# Bitsy_Display_Add-On.net
KiCad netlist of a schematic drawn in EAGLE
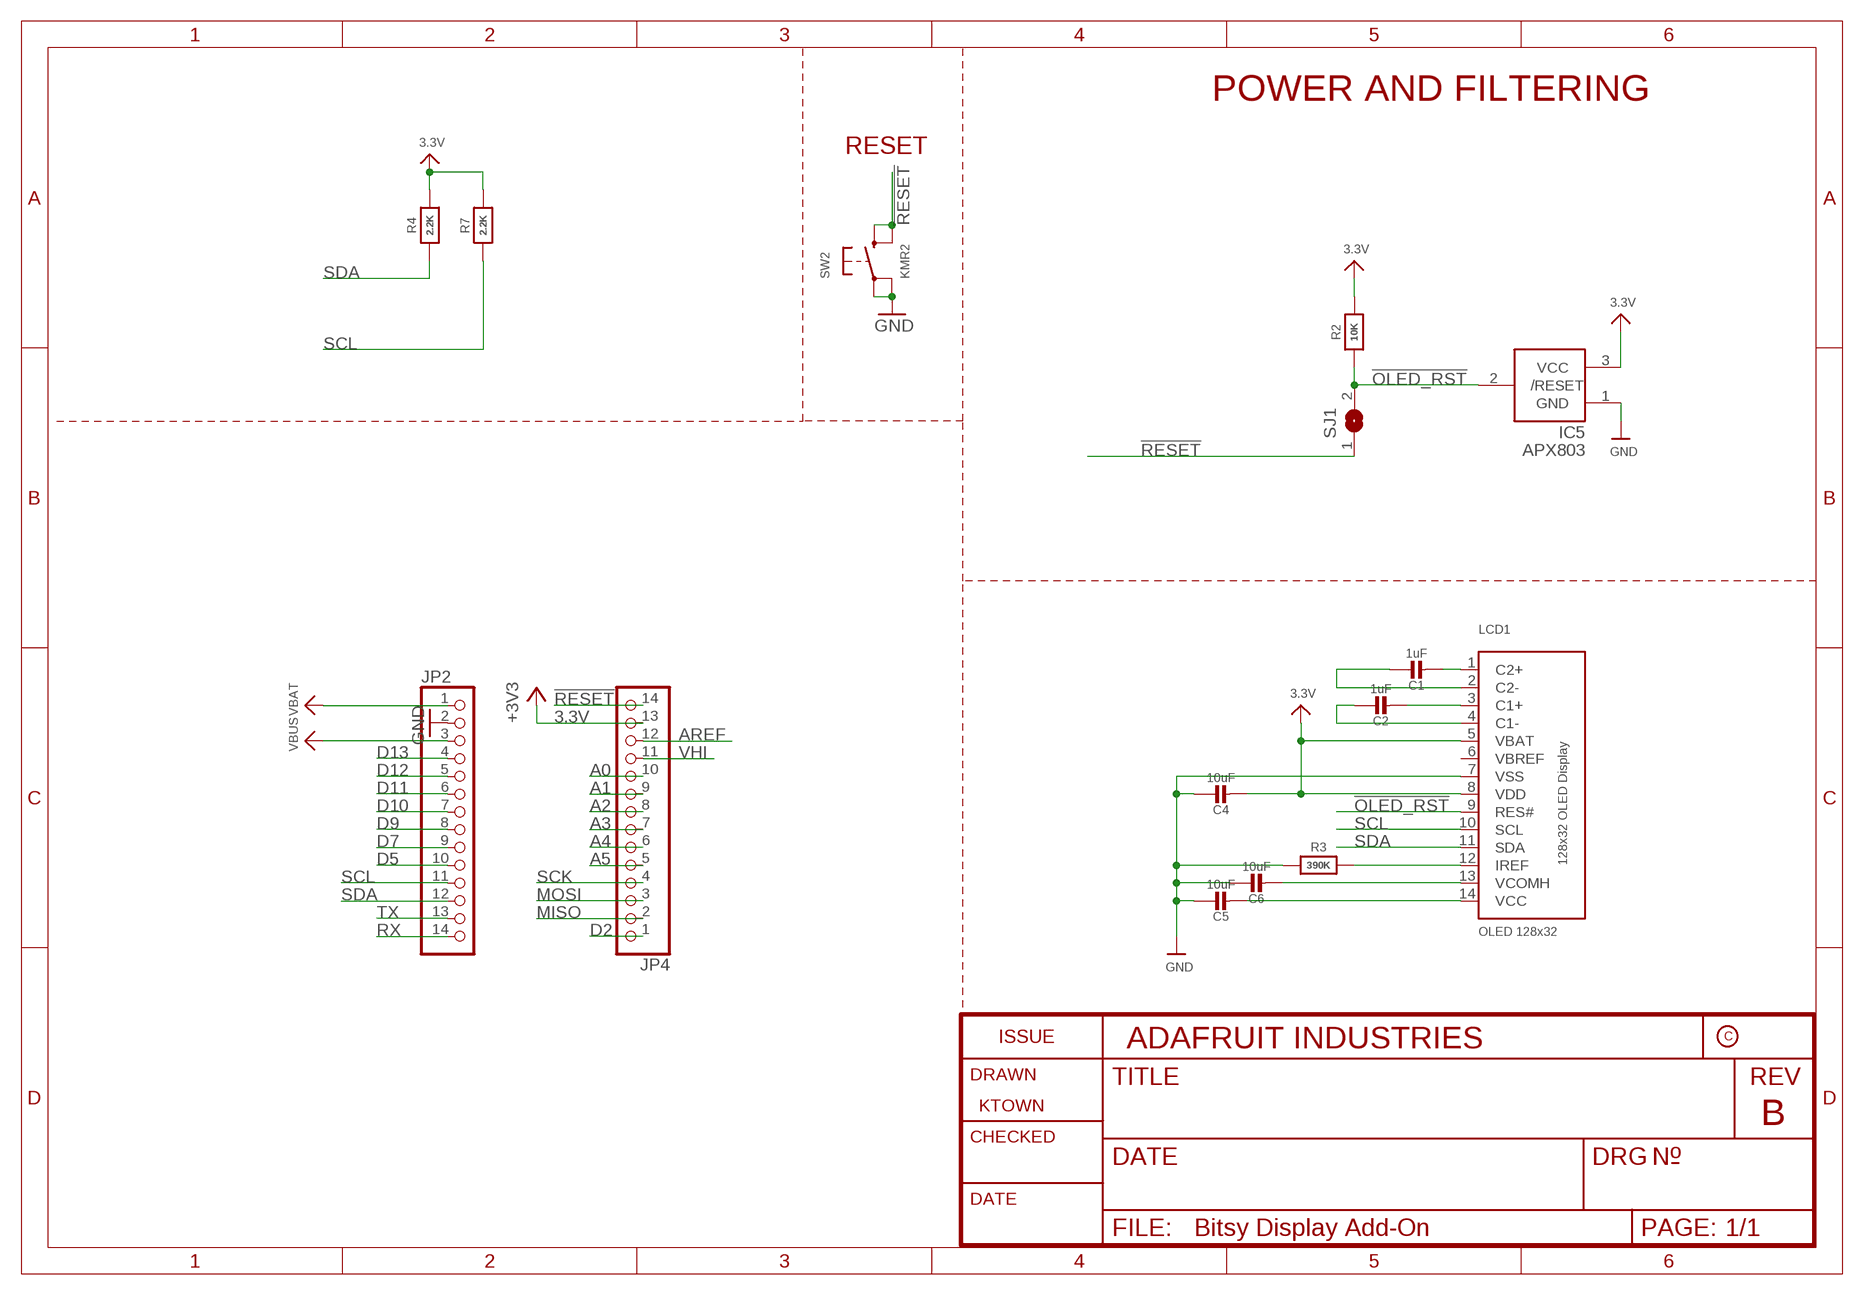
[diagram p0: schematic, sheet 1]

(export (version "E")
  (design (tool "Eeschema 10.0.6"))
  (components
    (comp (ref "C1")
      (value "1uF")
      (footprint "eagle-import:0805-NO")
      (libsource (lib "eagle-import") (part "CAP_CERAMIC0805-NOOUTLINE"))
    )
    (comp (ref "C2")
      (value "1uF")
      (footprint "eagle-import:0805-NO")
      (libsource (lib "eagle-import") (part "CAP_CERAMIC0805-NOOUTLINE"))
    )
    (comp (ref "C4")
      (value "10uF")
      (footprint "eagle-import:0805-NO")
      (libsource (lib "eagle-import") (part "CAP_CERAMIC0805-NOOUTLINE"))
    )
    (comp (ref "C5")
      (value "10uF")
      (footprint "eagle-import:0805-NO")
      (libsource (lib "eagle-import") (part "CAP_CERAMIC0805-NOOUTLINE"))
    )
    (comp (ref "C6")
      (value "10uF")
      (footprint "eagle-import:0805-NO")
      (libsource (lib "eagle-import") (part "CAP_CERAMIC0805-NOOUTLINE"))
    )
    (comp (ref "IC5")
      (value "APX803")
      (footprint "eagle-import:SOT23")
      (libsource (lib "eagle-import") (part "AXP083-SAG"))
    )
    (comp (ref "JP2")
      (value "HEADER-1X14")
      (footprint "eagle-import:1X14_ROUND70")
      (libsource (lib "eagle-import") (part "HEADER-1X14"))
    )
    (comp (ref "JP4")
      (value "HEADER-1X14")
      (footprint "eagle-import:1X14_ROUND70")
      (libsource (lib "eagle-import") (part "HEADER-1X14"))
    )
    (comp (ref "LCD1")
      (value "OLED 128x32")
      (footprint "eagle-import:UG-2832HSWEG02_WRAPUNDER")
      (libsource (lib "eagle-import") (part "DISP_OLED_UG-2832HSWEG02"))
    )
    (comp (ref "R2")
      (value "10K")
      (footprint "eagle-import:_0805MP")
      (libsource (lib "eagle-import") (part "RESISTOR_0805MP"))
    )
    (comp (ref "R3")
      (value "390K")
      (footprint "eagle-import:0805-NO")
      (libsource (lib "eagle-import") (part "RESISTOR0805_NOOUTLINE"))
    )
    (comp (ref "R4")
      (value "2.2K")
      (footprint "eagle-import:0805-NO")
      (libsource (lib "eagle-import") (part "RESISTOR0805_NOOUTLINE"))
    )
    (comp (ref "R7")
      (value "2.2K")
      (footprint "eagle-import:0805-NO")
      (libsource (lib "eagle-import") (part "RESISTOR0805_NOOUTLINE"))
    )
    (comp (ref "SJ1")
      (value "SOLDERJUMPER")
      (footprint "eagle-import:SOLDERJUMPER_ARROW_NOPASTE")
      (libsource (lib "eagle-import") (part "SOLDERJUMPER"))
    )
    (comp (ref "SW2")
      (value "KMR2")
      (footprint "eagle-import:BTN_KMR2_4.6X2.8")
      (libsource (lib "eagle-import") (part "SWITCH_TACT_SMT4.6X2.8"))
    )
  )
  (nets
    (net (code "1") (name "+3V3") (class "Default")
      (node (ref "C4") (pin "2") (pinfunction "2_2") (pintype "passive"))
      (node (ref "IC5") (pin "3") (pinfunction "VCC_3") (pintype "power_in"))
      (node (ref "JP4") (pin "13") (pinfunction "13_13") (pintype "passive"))
      (node (ref "LCD1") (pin "5") (pinfunction "VBAT_5") (pintype "power_in"))
      (node (ref "LCD1") (pin "8") (pinfunction "VDD_8") (pintype "power_in"))
      (node (ref "R2") (pin "2") (pinfunction "2_2") (pintype "passive"))
      (node (ref "R4") (pin "2") (pinfunction "2_2") (pintype "passive"))
      (node (ref "R7") (pin "2") (pinfunction "2_2") (pintype "passive"))
    )
    (net (code "2") (name "/A0") (class "Default")
      (node (ref "JP4") (pin "10") (pinfunction "10_10") (pintype "passive"))
    )
    (net (code "3") (name "/A1") (class "Default")
      (node (ref "JP4") (pin "9") (pinfunction "9_9") (pintype "passive"))
    )
    (net (code "4") (name "/A2") (class "Default")
      (node (ref "JP4") (pin "8") (pinfunction "8_8") (pintype "passive"))
    )
    (net (code "5") (name "/A3") (class "Default")
      (node (ref "JP4") (pin "7") (pinfunction "7_7") (pintype "passive"))
    )
    (net (code "6") (name "/A4") (class "Default")
      (node (ref "JP4") (pin "6") (pinfunction "6_6") (pintype "passive"))
    )
    (net (code "7") (name "/A5") (class "Default")
      (node (ref "JP4") (pin "5") (pinfunction "5_5") (pintype "passive"))
    )
    (net (code "8") (name "/AREF") (class "Default")
      (node (ref "JP4") (pin "12") (pinfunction "12_12") (pintype "passive"))
    )
    (net (code "9") (name "/D2") (class "Default")
      (node (ref "JP4") (pin "1") (pinfunction "1_1") (pintype "passive"))
    )
    (net (code "10") (name "/D5") (class "Default")
      (node (ref "JP2") (pin "10") (pinfunction "10_10") (pintype "passive"))
    )
    (net (code "11") (name "/D7") (class "Default")
      (node (ref "JP2") (pin "9") (pinfunction "9_9") (pintype "passive"))
    )
    (net (code "12") (name "/D9") (class "Default")
      (node (ref "JP2") (pin "8") (pinfunction "8_8") (pintype "passive"))
    )
    (net (code "13") (name "/D10") (class "Default")
      (node (ref "JP2") (pin "7") (pinfunction "7_7") (pintype "passive"))
    )
    (net (code "14") (name "/D11") (class "Default")
      (node (ref "JP2") (pin "6") (pinfunction "6_6") (pintype "passive"))
    )
    (net (code "15") (name "/D12") (class "Default")
      (node (ref "JP2") (pin "5") (pinfunction "5_5") (pintype "passive"))
    )
    (net (code "16") (name "/D13") (class "Default")
      (node (ref "JP2") (pin "4") (pinfunction "4_4") (pintype "passive"))
    )
    (net (code "17") (name "/MISO") (class "Default")
      (node (ref "JP4") (pin "2") (pinfunction "2_2") (pintype "passive"))
    )
    (net (code "18") (name "/MOSI") (class "Default")
      (node (ref "JP4") (pin "3") (pinfunction "3_3") (pintype "passive"))
    )
    (net (code "19") (name "/RX") (class "Default")
      (node (ref "JP2") (pin "14") (pinfunction "14_14") (pintype "passive"))
    )
    (net (code "20") (name "/SCK") (class "Default")
      (node (ref "JP4") (pin "4") (pinfunction "4_4") (pintype "passive"))
    )
    (net (code "21") (name "/SCL") (class "Default")
      (node (ref "JP2") (pin "11") (pinfunction "11_11") (pintype "passive"))
      (node (ref "LCD1") (pin "10") (pinfunction "SCL_10") (pintype "bidirectional"))
      (node (ref "R7") (pin "1") (pinfunction "1_1") (pintype "passive"))
    )
    (net (code "22") (name "/SDA") (class "Default")
      (node (ref "JP2") (pin "12") (pinfunction "12_12") (pintype "passive"))
      (node (ref "LCD1") (pin "11") (pinfunction "SDA_11") (pintype "bidirectional"))
      (node (ref "R4") (pin "1") (pinfunction "1_1") (pintype "passive"))
    )
    (net (code "23") (name "/TX") (class "Default")
      (node (ref "JP2") (pin "13") (pinfunction "13_13") (pintype "passive"))
    )
    (net (code "24") (name "/VBREF") (class "Default")
      (node (ref "LCD1") (pin "6") (pinfunction "VBREF_6") (pintype "power_in"))
    )
    (net (code "25") (name "/VHI") (class "Default")
      (node (ref "JP4") (pin "11") (pinfunction "11_11") (pintype "passive"))
    )
    (net (code "26") (name "/~{OLED_RST}") (class "Default")
      (node (ref "IC5") (pin "2") (pinfunction "/RESET_2") (pintype "output"))
      (node (ref "LCD1") (pin "9") (pinfunction "RES#_9") (pintype "bidirectional"))
      (node (ref "R2") (pin "1") (pinfunction "1_1") (pintype "passive"))
      (node (ref "SJ1") (pin "2") (pinfunction "2_2") (pintype "passive"))
    )
    (net (code "27") (name "/~{RESET}") (class "Default")
      (node (ref "JP4") (pin "14") (pinfunction "14_14") (pintype "passive"))
      (node (ref "SJ1") (pin "1") (pinfunction "1_1") (pintype "passive"))
      (node (ref "SW2") (pin "B") (pinfunction "S_B") (pintype "passive"))
      (node (ref "SW2") (pin "B'") (pinfunction "S1_B'") (pintype "passive"))
    )
    (net (code "28") (name "GND") (class "Default")
      (node (ref "C4") (pin "1") (pinfunction "1_1") (pintype "passive"))
      (node (ref "C5") (pin "1") (pinfunction "1_1") (pintype "passive"))
      (node (ref "C6") (pin "1") (pinfunction "1_1") (pintype "passive"))
      (node (ref "IC5") (pin "1") (pinfunction "GND_1") (pintype "power_in"))
      (node (ref "JP2") (pin "2") (pinfunction "2_2") (pintype "passive"))
      (node (ref "LCD1") (pin "7") (pinfunction "VSS_7") (pintype "power_in"))
      (node (ref "R3") (pin "1") (pinfunction "1_1") (pintype "passive"))
      (node (ref "SW2") (pin "A") (pinfunction "P_A") (pintype "passive"))
      (node (ref "SW2") (pin "A'") (pinfunction "P1_A'") (pintype "passive"))
    )
    (net (code "29") (name "Net-(LCD1-C1+)") (class "Default")
      (node (ref "C2") (pin "2") (pinfunction "2_2") (pintype "passive"))
      (node (ref "LCD1") (pin "3") (pinfunction "C1+_3") (pintype "bidirectional"))
    )
    (net (code "30") (name "Net-(LCD1-C1-)") (class "Default")
      (node (ref "C2") (pin "1") (pinfunction "1_1") (pintype "passive"))
      (node (ref "LCD1") (pin "4") (pinfunction "C1-_4") (pintype "bidirectional"))
    )
    (net (code "31") (name "Net-(LCD1-C2+)") (class "Default")
      (node (ref "C1") (pin "2") (pinfunction "2_2") (pintype "passive"))
      (node (ref "LCD1") (pin "1") (pinfunction "C2+_1") (pintype "bidirectional"))
    )
    (net (code "32") (name "Net-(LCD1-C2-)") (class "Default")
      (node (ref "C1") (pin "1") (pinfunction "1_1") (pintype "passive"))
      (node (ref "LCD1") (pin "2") (pinfunction "C2-_2") (pintype "bidirectional"))
    )
    (net (code "33") (name "Net-(LCD1-IREF)") (class "Default")
      (node (ref "LCD1") (pin "12") (pinfunction "IREF_12") (pintype "bidirectional"))
      (node (ref "R3") (pin "2") (pinfunction "2_2") (pintype "passive"))
    )
    (net (code "34") (name "Net-(LCD1-VCC)") (class "Default")
      (node (ref "C5") (pin "2") (pinfunction "2_2") (pintype "passive"))
      (node (ref "LCD1") (pin "14") (pinfunction "VCC_14") (pintype "power_in"))
    )
    (net (code "35") (name "Net-(LCD1-VCOMH)") (class "Default")
      (node (ref "C6") (pin "2") (pinfunction "2_2") (pintype "passive"))
      (node (ref "LCD1") (pin "13") (pinfunction "VCOMH_13") (pintype "power_in"))
    )
    (net (code "36") (name "VBAT") (class "Default")
      (node (ref "JP2") (pin "1") (pinfunction "1_1") (pintype "passive"))
    )
    (net (code "37") (name "VBUS") (class "Default")
      (node (ref "JP2") (pin "3") (pinfunction "3_3") (pintype "passive"))
    )
  )
)
